# 1.net
KiCad netlist of a schematic drawn in Altium Designer
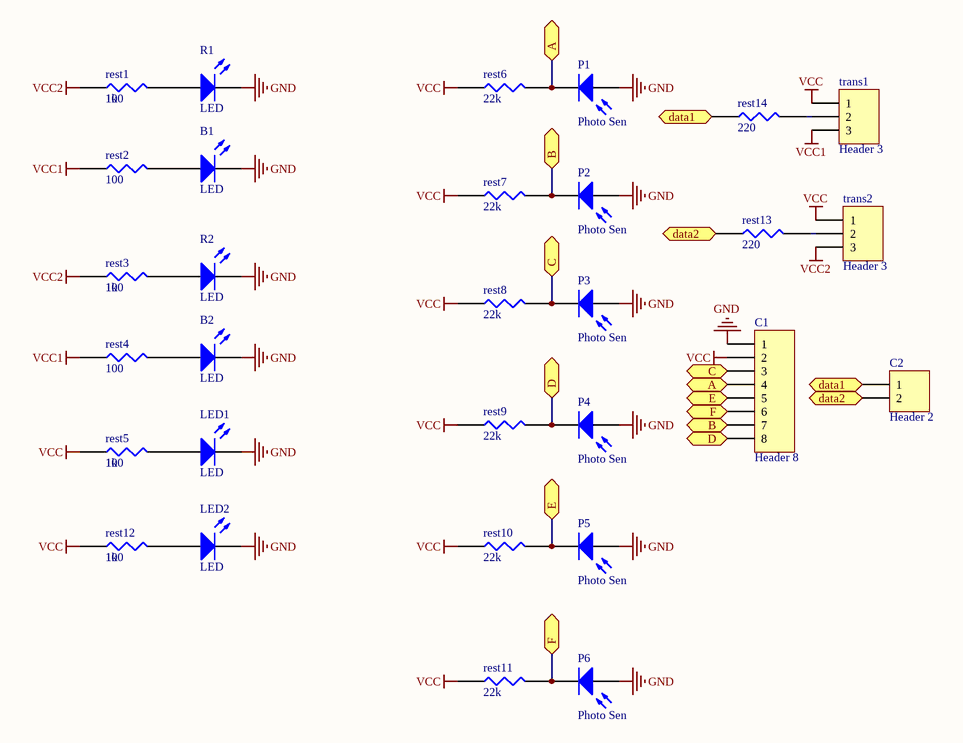
[diagram p0: 1.SchDoc]

(export (version "E")
  (design (tool "Eeschema 10.0.6"))
  (components
    (comp (ref "B1")
      (value "LED")
      (footprint "My_LED3MM")
      (description "Typical INFRARED GaAs LED")
      (fields (field (name "PUBLISHER") "Altium Limited"))
      (libsource (lib "Mylib") (part "LED"))
    )
    (comp (ref "B2")
      (value "LED")
      (footprint "My_LED3MM")
      (description "Typical INFRARED GaAs LED")
      (fields (field (name "PUBLISHER") "Altium Limited"))
      (libsource (lib "Mylib") (part "LED"))
    )
    (comp (ref "C1")
      (value "Header 8")
      (footprint "HDR1X8")
      (description "Header, 8-Pin")
      (fields (field (name "PUBLISHER") "Altium Limited"))
      (libsource (lib "Miscellaneous Connectors") (part "Header 8"))
    )
    (comp (ref "C2")
      (value "Header 2")
      (footprint "HDR1X2")
      (description "Header, 2-Pin")
      (fields (field (name "PUBLISHER") "Altium Limited"))
      (libsource (lib "Miscellaneous Connectors") (part "Header 2"))
    )
    (comp (ref "LED1")
      (value "LED")
      (footprint "My_LED3MM")
      (description "Typical INFRARED GaAs LED")
      (fields (field (name "PUBLISHER") "Altium Limited"))
      (libsource (lib "Mylib") (part "LED"))
    )
    (comp (ref "LED2")
      (value "LED")
      (footprint "My_LED3MM")
      (description "Typical INFRARED GaAs LED")
      (fields (field (name "PUBLISHER") "Altium Limited"))
      (libsource (lib "Mylib") (part "LED"))
    )
    (comp (ref "P1")
      (value "Photo Sen")
      (footprint "PIN2")
      (description "Photosensitive Diode")
      (fields (field (name "PUBLISHER") "Altium Limited"))
      (libsource (lib "Miscellaneous Devices") (part "Photo Sen"))
    )
    (comp (ref "P2")
      (value "Photo Sen")
      (footprint "PIN2")
      (description "Photosensitive Diode")
      (fields (field (name "PUBLISHER") "Altium Limited"))
      (libsource (lib "Miscellaneous Devices") (part "Photo Sen"))
    )
    (comp (ref "P3")
      (value "Photo Sen")
      (footprint "PIN2")
      (description "Photosensitive Diode")
      (fields (field (name "PUBLISHER") "Altium Limited"))
      (libsource (lib "Miscellaneous Devices") (part "Photo Sen"))
    )
    (comp (ref "P4")
      (value "Photo Sen")
      (footprint "PIN2")
      (description "Photosensitive Diode")
      (fields (field (name "PUBLISHER") "Altium Limited"))
      (libsource (lib "Miscellaneous Devices") (part "Photo Sen"))
    )
    (comp (ref "P5")
      (value "Photo Sen")
      (footprint "PIN2")
      (description "Photosensitive Diode")
      (fields (field (name "PUBLISHER") "Altium Limited"))
      (libsource (lib "Miscellaneous Devices") (part "Photo Sen"))
    )
    (comp (ref "P6")
      (value "Photo Sen")
      (footprint "PIN2")
      (description "Photosensitive Diode")
      (fields (field (name "PUBLISHER") "Altium Limited"))
      (libsource (lib "Miscellaneous Devices") (part "Photo Sen"))
    )
    (comp (ref "R1")
      (value "LED")
      (footprint "My_LED3MM")
      (description "Typical INFRARED GaAs LED")
      (fields (field (name "PUBLISHER") "Altium Limited"))
      (libsource (lib "Mylib") (part "LED"))
    )
    (comp (ref "R2")
      (value "LED")
      (footprint "My_LED3MM")
      (description "Typical INFRARED GaAs LED")
      (fields (field (name "PUBLISHER") "Altium Limited"))
      (libsource (lib "Mylib") (part "LED"))
    )
    (comp (ref "rest1")
      (value "1k")
      (footprint "AXIAL-0.3")
      (description "resistor 1/4 wat")
      (fields (field (name "ALTIUM_VALUE") "100"))
      (libsource (lib "Mylib") (part "Res"))
    )
    (comp (ref "rest2")
      (value "100")
      (footprint "AXIAL-0.3")
      (description "resistor 1/4 wat")
      (libsource (lib "Mylib") (part "Res"))
    )
    (comp (ref "rest3")
      (value "1k")
      (footprint "AXIAL-0.3")
      (description "resistor 1/4 wat")
      (fields (field (name "ALTIUM_VALUE") "100"))
      (libsource (lib "Mylib") (part "Res"))
    )
    (comp (ref "rest4")
      (value "100")
      (footprint "AXIAL-0.3")
      (description "resistor 1/4 wat")
      (libsource (lib "Mylib") (part "Res"))
    )
    (comp (ref "rest5")
      (value "1k")
      (footprint "AXIAL-0.3")
      (description "resistor 1/4 wat")
      (fields (field (name "ALTIUM_VALUE") "100"))
      (libsource (lib "Mylib") (part "Res"))
    )
    (comp (ref "rest6")
      (value "22k")
      (footprint "AXIAL-0.3")
      (description "resistor 1/4 wat")
      (fields (field (name "Comment") "1k"))
      (libsource (lib "Mylib") (part "Res"))
    )
    (comp (ref "rest7")
      (value "22k")
      (footprint "AXIAL-0.3")
      (description "resistor 1/4 wat")
      (fields (field (name "Comment") "1k"))
      (libsource (lib "Mylib") (part "Res"))
    )
    (comp (ref "rest8")
      (value "22k")
      (footprint "AXIAL-0.3")
      (description "resistor 1/4 wat")
      (fields (field (name "Comment") "1k"))
      (libsource (lib "Mylib") (part "Res"))
    )
    (comp (ref "rest9")
      (value "22k")
      (footprint "AXIAL-0.3")
      (description "resistor 1/4 wat")
      (fields (field (name "Comment") "1k"))
      (libsource (lib "Mylib") (part "Res"))
    )
    (comp (ref "rest10")
      (value "22k")
      (footprint "AXIAL-0.3")
      (description "resistor 1/4 wat")
      (fields (field (name "Comment") "1k"))
      (libsource (lib "Mylib") (part "Res"))
    )
    (comp (ref "rest11")
      (value "22k")
      (footprint "AXIAL-0.3")
      (description "resistor 1/4 wat")
      (fields (field (name "Comment") "1k"))
      (libsource (lib "Mylib") (part "Res"))
    )
    (comp (ref "rest12")
      (value "1k")
      (footprint "AXIAL-0.3")
      (description "resistor 1/4 wat")
      (fields (field (name "ALTIUM_VALUE") "100"))
      (libsource (lib "Mylib") (part "Res"))
    )
    (comp (ref "rest13")
      (value "220")
      (footprint "AXIAL-0.3")
      (description "resistor 1/4 wat")
      (fields (field (name "Comment") "1k"))
      (libsource (lib "Mylib") (part "Res"))
    )
    (comp (ref "rest14")
      (value "220")
      (footprint "AXIAL-0.3")
      (description "resistor 1/4 wat")
      (fields (field (name "Comment") "1k"))
      (libsource (lib "Mylib") (part "Res"))
    )
    (comp (ref "trans1")
      (value "Header 3")
      (footprint "HDR1X3")
      (description "Header, 3-Pin")
      (fields (field (name "PUBLISHER") "Altium Limited"))
      (libsource (lib "Miscellaneous Connectors") (part "Header 3"))
    )
    (comp (ref "trans2")
      (value "Header 3")
      (footprint "HDR1X3")
      (description "Header, 3-Pin")
      (fields (field (name "PUBLISHER") "Altium Limited"))
      (libsource (lib "Miscellaneous Connectors") (part "Header 3"))
    )
  )
  (nets
    (net (code "1") (name "/A") (class "Default")
      (node (ref "C1") (pin "4") (pinfunction "4_4") (pintype "passive"))
      (node (ref "P1") (pin "2") (pinfunction "K_2") (pintype "passive"))
      (node (ref "rest6") (pin "2") (pinfunction "2_2") (pintype "passive"))
    )
    (net (code "2") (name "/B") (class "Default")
      (node (ref "C1") (pin "7") (pinfunction "7_7") (pintype "passive"))
      (node (ref "P2") (pin "2") (pinfunction "K_2") (pintype "passive"))
      (node (ref "rest7") (pin "2") (pinfunction "2_2") (pintype "passive"))
    )
    (net (code "3") (name "/C") (class "Default")
      (node (ref "C1") (pin "3") (pinfunction "3_3") (pintype "passive"))
      (node (ref "P3") (pin "2") (pinfunction "K_2") (pintype "passive"))
      (node (ref "rest8") (pin "2") (pinfunction "2_2") (pintype "passive"))
    )
    (net (code "4") (name "/D") (class "Default")
      (node (ref "C1") (pin "8") (pinfunction "8_8") (pintype "passive"))
      (node (ref "P4") (pin "2") (pinfunction "K_2") (pintype "passive"))
      (node (ref "rest9") (pin "2") (pinfunction "2_2") (pintype "passive"))
    )
    (net (code "5") (name "/E") (class "Default")
      (node (ref "C1") (pin "5") (pinfunction "5_5") (pintype "passive"))
      (node (ref "P5") (pin "2") (pinfunction "K_2") (pintype "passive"))
      (node (ref "rest10") (pin "2") (pinfunction "2_2") (pintype "passive"))
    )
    (net (code "6") (name "/F") (class "Default")
      (node (ref "C1") (pin "6") (pinfunction "6_6") (pintype "passive"))
      (node (ref "P6") (pin "2") (pinfunction "K_2") (pintype "passive"))
      (node (ref "rest11") (pin "2") (pinfunction "2_2") (pintype "passive"))
    )
    (net (code "7") (name "/data1") (class "Default")
      (node (ref "C2") (pin "1") (pinfunction "1_1") (pintype "passive"))
      (node (ref "rest14") (pin "1") (pinfunction "1_1") (pintype "passive"))
    )
    (net (code "8") (name "/data2") (class "Default")
      (node (ref "C2") (pin "2") (pinfunction "2_2") (pintype "passive"))
      (node (ref "rest13") (pin "1") (pinfunction "1_1") (pintype "passive"))
    )
    (net (code "9") (name "GND") (class "Default")
      (node (ref "B1") (pin "K") (pinfunction "K_K") (pintype "passive"))
      (node (ref "B2") (pin "K") (pinfunction "K_K") (pintype "passive"))
      (node (ref "C1") (pin "1") (pinfunction "1_1") (pintype "passive"))
      (node (ref "LED1") (pin "K") (pinfunction "K_K") (pintype "passive"))
      (node (ref "LED2") (pin "K") (pinfunction "K_K") (pintype "passive"))
      (node (ref "P1") (pin "1") (pinfunction "A_1") (pintype "passive"))
      (node (ref "P2") (pin "1") (pinfunction "A_1") (pintype "passive"))
      (node (ref "P3") (pin "1") (pinfunction "A_1") (pintype "passive"))
      (node (ref "P4") (pin "1") (pinfunction "A_1") (pintype "passive"))
      (node (ref "P5") (pin "1") (pinfunction "A_1") (pintype "passive"))
      (node (ref "P6") (pin "1") (pinfunction "A_1") (pintype "passive"))
      (node (ref "R1") (pin "K") (pinfunction "K_K") (pintype "passive"))
      (node (ref "R2") (pin "K") (pinfunction "K_K") (pintype "passive"))
    )
    (net (code "10") (name "Net-(B1-PadA)") (class "Default")
      (node (ref "B1") (pin "A") (pinfunction "A_A") (pintype "passive"))
      (node (ref "rest2") (pin "2") (pinfunction "2_2") (pintype "passive"))
    )
    (net (code "11") (name "Net-(B2-PadA)") (class "Default")
      (node (ref "B2") (pin "A") (pinfunction "A_A") (pintype "passive"))
      (node (ref "rest4") (pin "2") (pinfunction "2_2") (pintype "passive"))
    )
    (net (code "12") (name "Net-(LED1-PadA)") (class "Default")
      (node (ref "LED1") (pin "A") (pinfunction "A_A") (pintype "passive"))
      (node (ref "rest5") (pin "2") (pinfunction "2_2") (pintype "passive"))
    )
    (net (code "13") (name "Net-(LED2-PadA)") (class "Default")
      (node (ref "LED2") (pin "A") (pinfunction "A_A") (pintype "passive"))
      (node (ref "rest12") (pin "2") (pinfunction "2_2") (pintype "passive"))
    )
    (net (code "14") (name "Net-(R1-PadA)") (class "Default")
      (node (ref "R1") (pin "A") (pinfunction "A_A") (pintype "passive"))
      (node (ref "rest1") (pin "2") (pinfunction "2_2") (pintype "passive"))
    )
    (net (code "15") (name "Net-(R2-PadA)") (class "Default")
      (node (ref "R2") (pin "A") (pinfunction "A_A") (pintype "passive"))
      (node (ref "rest3") (pin "2") (pinfunction "2_2") (pintype "passive"))
    )
    (net (code "16") (name "Net-(rest13-Pad2)") (class "Default")
      (node (ref "rest13") (pin "2") (pinfunction "2_2") (pintype "passive"))
      (node (ref "trans2") (pin "2") (pinfunction "2_2") (pintype "passive"))
    )
    (net (code "17") (name "Net-(rest14-Pad2)") (class "Default")
      (node (ref "rest14") (pin "2") (pinfunction "2_2") (pintype "passive"))
      (node (ref "trans1") (pin "2") (pinfunction "2_2") (pintype "passive"))
    )
    (net (code "18") (name "VCC") (class "Default")
      (node (ref "C1") (pin "2") (pinfunction "2_2") (pintype "passive"))
      (node (ref "rest10") (pin "1") (pinfunction "1_1") (pintype "passive"))
      (node (ref "rest11") (pin "1") (pinfunction "1_1") (pintype "passive"))
      (node (ref "rest12") (pin "1") (pinfunction "1_1") (pintype "passive"))
      (node (ref "rest5") (pin "1") (pinfunction "1_1") (pintype "passive"))
      (node (ref "rest6") (pin "1") (pinfunction "1_1") (pintype "passive"))
      (node (ref "rest7") (pin "1") (pinfunction "1_1") (pintype "passive"))
      (node (ref "rest8") (pin "1") (pinfunction "1_1") (pintype "passive"))
      (node (ref "rest9") (pin "1") (pinfunction "1_1") (pintype "passive"))
      (node (ref "trans1") (pin "1") (pinfunction "1_1") (pintype "passive"))
      (node (ref "trans2") (pin "1") (pinfunction "1_1") (pintype "passive"))
    )
    (net (code "19") (name "VCC1") (class "Default")
      (node (ref "rest2") (pin "1") (pinfunction "1_1") (pintype "passive"))
      (node (ref "rest4") (pin "1") (pinfunction "1_1") (pintype "passive"))
      (node (ref "trans1") (pin "3") (pinfunction "3_3") (pintype "passive"))
    )
    (net (code "20") (name "VCC2") (class "Default")
      (node (ref "rest1") (pin "1") (pinfunction "1_1") (pintype "passive"))
      (node (ref "rest3") (pin "1") (pinfunction "1_1") (pintype "passive"))
      (node (ref "trans2") (pin "3") (pinfunction "3_3") (pintype "passive"))
    )
  )
)
